# 3_-DAC.net
KiCad netlist of a schematic drawn in Altium Designer
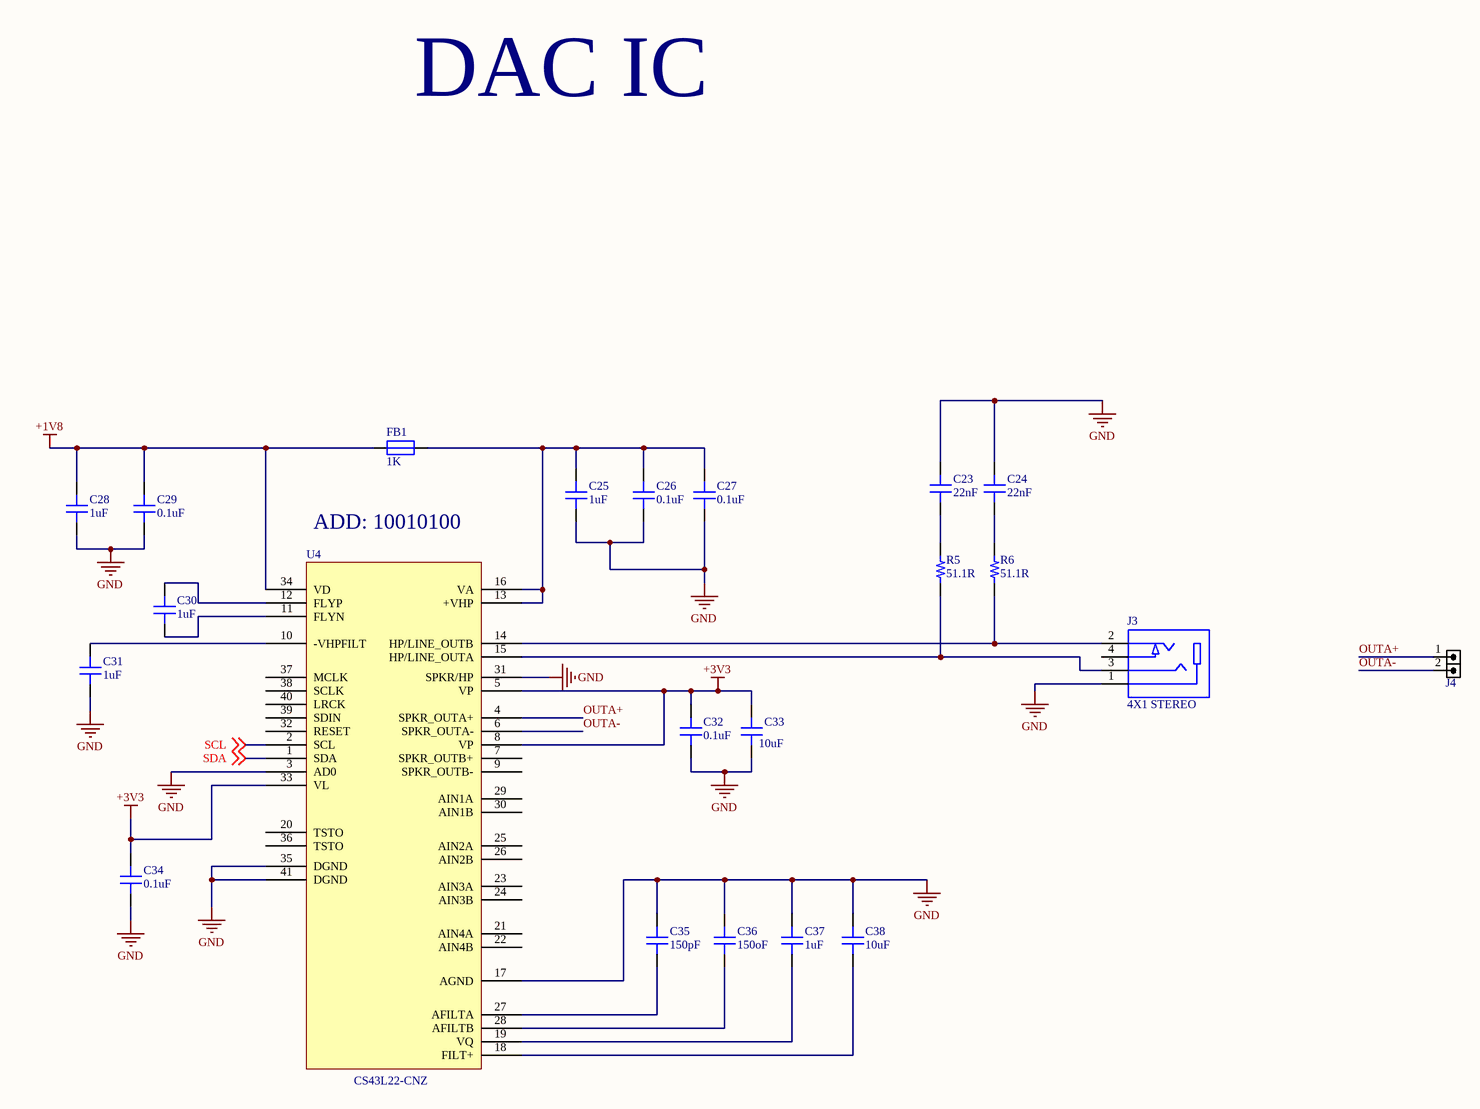
[diagram p0: [3]-DAC.SchDoc]

(export (version "E")
  (design (tool "Eeschema 10.0.6"))
  (components
    (comp (ref "C23")
      (value "22nF")
      (footprint "CAP 0603_1608")
      (description "SMT Capacitor")
      (libsource (lib "Capacitor") (part "Cap 0603"))
    )
    (comp (ref "C24")
      (value "22nF")
      (footprint "CAP 0603_1608")
      (description "SMT Capacitor")
      (libsource (lib "Capacitor") (part "Cap 0603"))
    )
    (comp (ref "C25")
      (value "1uF")
      (footprint "CAP 0603_1608")
      (description "SMT Capacitor")
      (libsource (lib "Capacitor") (part "Cap 0603"))
    )
    (comp (ref "C26")
      (value "0.1uF")
      (footprint "CAP 0603_1608")
      (description "SMT Capacitor")
      (libsource (lib "Capacitor") (part "Cap 0603"))
    )
    (comp (ref "C27")
      (value "0.1uF")
      (footprint "CAP 0603_1608")
      (description "SMT Capacitor")
      (libsource (lib "Capacitor") (part "Cap 0603"))
    )
    (comp (ref "C28")
      (value "1uF")
      (footprint "CAP 0603_1608")
      (description "SMT Capacitor")
      (libsource (lib "Capacitor") (part "Cap 0603"))
    )
    (comp (ref "C29")
      (value "0.1uF")
      (footprint "CAP 0603_1608")
      (description "SMT Capacitor")
      (libsource (lib "Capacitor") (part "Cap 0603"))
    )
    (comp (ref "C30")
      (value "1uF")
      (footprint "CAP 0603_1608")
      (description "SMT Capacitor")
      (libsource (lib "Capacitor") (part "Cap 0603"))
    )
    (comp (ref "C31")
      (value "1uF")
      (footprint "CAP 0603_1608")
      (description "SMT Capacitor")
      (libsource (lib "Capacitor") (part "Cap 0603"))
    )
    (comp (ref "C32")
      (value "0.1uF")
      (footprint "CAP 0603_1608")
      (description "SMT Capacitor")
      (libsource (lib "Capacitor") (part "Cap 0603"))
    )
    (comp (ref "C33")
      (value "10uF")
      (footprint "CAP 0603_1608")
      (description "SMT Capacitor")
      (libsource (lib "Capacitor") (part "Cap 0603"))
    )
    (comp (ref "C34")
      (value "0.1uF")
      (footprint "CAP 0603_1608")
      (description "SMT Capacitor")
      (libsource (lib "Capacitor") (part "Cap 0603"))
    )
    (comp (ref "C35")
      (value "150pF")
      (footprint "CAP 0603_1608")
      (description "SMT Capacitor")
      (libsource (lib "Capacitor") (part "Cap 0603"))
    )
    (comp (ref "C36")
      (value "150oF")
      (footprint "CAP 0603_1608")
      (description "SMT Capacitor")
      (libsource (lib "Capacitor") (part "Cap 0603"))
    )
    (comp (ref "C37")
      (value "1uF")
      (footprint "CAP 0603_1608")
      (description "SMT Capacitor")
      (libsource (lib "Capacitor") (part "Cap 0603"))
    )
    (comp (ref "C38")
      (value "10uF")
      (footprint "CAP 0603_1608")
      (description "SMT Capacitor")
      (libsource (lib "Capacitor") (part "Cap 0603"))
    )
    (comp (ref "FB1")
      (value "1K")
      (footprint "IND_0805")
      (description "1 kOhms @ 100MHz 1 Power Line Ferrite Bead 0805 (2012 Metric) 1.6A")
      (fields
        (field (name "MANUFACTURER") "Laird")
        (field (name "MANUFACTURER PART NUMBER") "BLM21SP102SH1D")
      )
      (libsource (lib "ESTEEMPCBLIB") (part "FB_1K-100MHZ-1.6A-0805"))
    )
    (comp (ref "J3")
      (value "4X1 STEREO")
      (footprint "CON_SJ-2504A-SMT-TR_SMD")
      (fields
        (field (name "MANUFACTURER") "CUI Devices")
        (field (name "MANUFACTURER PART NUMBER") "SJ-2504A-SMT-TR")
      )
      (libsource (lib "ESTEEMPCBLIB") (part "CON-PLG-STEREO_4X1-100-RA-SMD"))
    )
    (comp (ref "J4")
      (value "HDR2")
      (footprint "HDR1SE_M_1X2")
      (description "HEADER, 1mm pitch, test, SMD")
      (libsource (lib "Conn Header") (part "HDRTST_1X2"))
    )
    (comp (ref "R5")
      (value "51.1R")
      (footprint "RES 0603_1608")
      (description "SMT Resistor")
      (libsource (lib "Resistor") (part "Res 0603"))
    )
    (comp (ref "R6")
      (value "51.1R")
      (footprint "RES 0603_1608")
      (description "SMT Resistor")
      (libsource (lib "Resistor") (part "Res 0603"))
    )
    (comp (ref "U4")
      (value "CS43L22-CNZ")
      (footprint "QFN40_19_284_33X9_SMD")
      (description "Audio D/A Converter ICs Low Power Stereo DAC w/ClassD Spkr Driver")
      (fields (field (name "MANUFACTURER") "Cirrus Logic"))
      (libsource (lib "ESTEEMPCBLIB") (part "IC_CS43L22"))
    )
  )
  (nets
    (net (code "1") (name "+1V8") (class "Default")
      (node (ref "C28") (pin "2") (pinfunction "2_2") (pintype "passive"))
      (node (ref "C29") (pin "2") (pinfunction "2_2") (pintype "passive"))
      (node (ref "FB1") (pin "1") (pinfunction "1_1") (pintype "passive"))
      (node (ref "U4") (pin "34") (pinfunction "VD_34") (pintype "passive"))
    )
    (net (code "2") (name "+3V3") (class "Default")
      (node (ref "C32") (pin "2") (pinfunction "2_2") (pintype "passive"))
      (node (ref "C33") (pin "2") (pinfunction "2_2") (pintype "passive"))
      (node (ref "C34") (pin "2") (pinfunction "2_2") (pintype "passive"))
      (node (ref "U4") (pin "33") (pinfunction "VL_33") (pintype "passive"))
      (node (ref "U4") (pin "5") (pinfunction "VP_5") (pintype "passive"))
      (node (ref "U4") (pin "8") (pinfunction "VP_8") (pintype "passive"))
    )
    (net (code "3") (name "/OUTA+") (class "Default")
      (node (ref "J4") (pin "1") (pinfunction "1_1") (pintype "passive"))
      (node (ref "U4") (pin "4") (pinfunction "SPKR_OUTA+_4") (pintype "passive"))
    )
    (net (code "4") (name "/OUTA-") (class "Default")
      (node (ref "J4") (pin "2") (pinfunction "2_2") (pintype "passive"))
      (node (ref "U4") (pin "6") (pinfunction "SPKR_OUTA-_6") (pintype "passive"))
    )
    (net (code "5") (name "GND") (class "Default")
      (node (ref "C23") (pin "2") (pinfunction "2_2") (pintype "passive"))
      (node (ref "C24") (pin "2") (pinfunction "2_2") (pintype "passive"))
      (node (ref "C25") (pin "1") (pinfunction "1_1") (pintype "passive"))
      (node (ref "C26") (pin "1") (pinfunction "1_1") (pintype "passive"))
      (node (ref "C27") (pin "1") (pinfunction "1_1") (pintype "passive"))
      (node (ref "C28") (pin "1") (pinfunction "1_1") (pintype "passive"))
      (node (ref "C29") (pin "1") (pinfunction "1_1") (pintype "passive"))
      (node (ref "C31") (pin "1") (pinfunction "1_1") (pintype "passive"))
      (node (ref "C32") (pin "1") (pinfunction "1_1") (pintype "passive"))
      (node (ref "C33") (pin "1") (pinfunction "1_1") (pintype "passive"))
      (node (ref "C34") (pin "1") (pinfunction "1_1") (pintype "passive"))
      (node (ref "C35") (pin "2") (pinfunction "2_2") (pintype "passive"))
      (node (ref "C36") (pin "2") (pinfunction "2_2") (pintype "passive"))
      (node (ref "C37") (pin "2") (pinfunction "2_2") (pintype "passive"))
      (node (ref "C38") (pin "2") (pinfunction "2_2") (pintype "passive"))
      (node (ref "J3") (pin "1") (pinfunction "1_1") (pintype "passive"))
      (node (ref "U4") (pin "17") (pinfunction "AGND_17") (pintype "passive"))
      (node (ref "U4") (pin "3") (pinfunction "AD0_3") (pintype "passive"))
      (node (ref "U4") (pin "31") (pinfunction "SPKR/HP_31") (pintype "passive"))
      (node (ref "U4") (pin "35") (pinfunction "DGND_35") (pintype "passive"))
      (node (ref "U4") (pin "41") (pinfunction "DGND_41") (pintype "passive"))
    )
    (net (code "6") (name "Net-(C23-Pad1)") (class "Default")
      (node (ref "C23") (pin "1") (pinfunction "1_1") (pintype "passive"))
      (node (ref "R5") (pin "2") (pinfunction "2_2") (pintype "passive"))
    )
    (net (code "7") (name "Net-(C24-Pad1)") (class "Default")
      (node (ref "C24") (pin "1") (pinfunction "1_1") (pintype "passive"))
      (node (ref "R6") (pin "2") (pinfunction "2_2") (pintype "passive"))
    )
    (net (code "8") (name "Net-(U4-+VHP)") (class "Default")
      (node (ref "C25") (pin "2") (pinfunction "2_2") (pintype "passive"))
      (node (ref "C26") (pin "2") (pinfunction "2_2") (pintype "passive"))
      (node (ref "C27") (pin "2") (pinfunction "2_2") (pintype "passive"))
      (node (ref "FB1") (pin "2") (pinfunction "2_2") (pintype "passive"))
      (node (ref "U4") (pin "13") (pinfunction "+VHP_13") (pintype "passive"))
      (node (ref "U4") (pin "16") (pinfunction "VA_16") (pintype "passive"))
    )
    (net (code "9") (name "Net-(U4--VHPFILT)") (class "Default")
      (node (ref "C31") (pin "2") (pinfunction "2_2") (pintype "passive"))
      (node (ref "U4") (pin "10") (pinfunction "-VHPFILT_10") (pintype "passive"))
    )
    (net (code "10") (name "Net-(U4-AFILTA)") (class "Default")
      (node (ref "C35") (pin "1") (pinfunction "1_1") (pintype "passive"))
      (node (ref "U4") (pin "27") (pinfunction "AFILTA_27") (pintype "passive"))
    )
    (net (code "11") (name "Net-(U4-AFILTB)") (class "Default")
      (node (ref "C36") (pin "1") (pinfunction "1_1") (pintype "passive"))
      (node (ref "U4") (pin "28") (pinfunction "AFILTB_28") (pintype "passive"))
    )
    (net (code "12") (name "Net-(U4-FILT+)") (class "Default")
      (node (ref "C38") (pin "1") (pinfunction "1_1") (pintype "passive"))
      (node (ref "U4") (pin "18") (pinfunction "FILT+_18") (pintype "passive"))
    )
    (net (code "13") (name "Net-(U4-FLYN)") (class "Default")
      (node (ref "C30") (pin "2") (pinfunction "2_2") (pintype "passive"))
      (node (ref "U4") (pin "11") (pinfunction "FLYN_11") (pintype "passive"))
    )
    (net (code "14") (name "Net-(U4-FLYP)") (class "Default")
      (node (ref "C30") (pin "1") (pinfunction "1_1") (pintype "passive"))
      (node (ref "U4") (pin "12") (pinfunction "FLYP_12") (pintype "passive"))
    )
    (net (code "15") (name "Net-(U4-HP{slash}LINE_OUTA)") (class "Default")
      (node (ref "J3") (pin "3") (pinfunction "3_3") (pintype "passive"))
      (node (ref "R5") (pin "1") (pinfunction "1_1") (pintype "passive"))
      (node (ref "U4") (pin "15") (pinfunction "HP/LINE_OUTA_15") (pintype "passive"))
    )
    (net (code "16") (name "Net-(U4-HP{slash}LINE_OUTB)") (class "Default")
      (node (ref "J3") (pin "2") (pinfunction "2_2") (pintype "passive"))
      (node (ref "R6") (pin "1") (pinfunction "1_1") (pintype "passive"))
      (node (ref "U4") (pin "14") (pinfunction "HP/LINE_OUTB_14") (pintype "passive"))
    )
    (net (code "17") (name "Net-(U4-VQ)") (class "Default")
      (node (ref "C37") (pin "1") (pinfunction "1_1") (pintype "passive"))
      (node (ref "U4") (pin "19") (pinfunction "VQ_19") (pintype "passive"))
    )
    (net (code "18") (name "SCL") (class "Default")
      (node (ref "U4") (pin "2") (pinfunction "SCL_2") (pintype "passive"))
    )
    (net (code "19") (name "SDA") (class "Default")
      (node (ref "U4") (pin "1") (pinfunction "SDA_1") (pintype "passive"))
    )
    (net (code "20") (name "unconnected-(J3-Pad4)") (class "Default")
      (node (ref "J3") (pin "4") (pinfunction "4_4") (pintype "passive"))
    )
    (net (code "21") (name "unconnected-(U4-AIN1A-Pad29)") (class "Default")
      (node (ref "U4") (pin "29") (pinfunction "AIN1A_29") (pintype "passive"))
    )
    (net (code "22") (name "unconnected-(U4-AIN1B-Pad30)") (class "Default")
      (node (ref "U4") (pin "30") (pinfunction "AIN1B_30") (pintype "passive"))
    )
    (net (code "23") (name "unconnected-(U4-AIN2A-Pad25)") (class "Default")
      (node (ref "U4") (pin "25") (pinfunction "AIN2A_25") (pintype "passive"))
    )
    (net (code "24") (name "unconnected-(U4-AIN2B-Pad26)") (class "Default")
      (node (ref "U4") (pin "26") (pinfunction "AIN2B_26") (pintype "passive"))
    )
    (net (code "25") (name "unconnected-(U4-AIN3A-Pad23)") (class "Default")
      (node (ref "U4") (pin "23") (pinfunction "AIN3A_23") (pintype "passive"))
    )
    (net (code "26") (name "unconnected-(U4-AIN3B-Pad24)") (class "Default")
      (node (ref "U4") (pin "24") (pinfunction "AIN3B_24") (pintype "passive"))
    )
    (net (code "27") (name "unconnected-(U4-AIN4A-Pad21)") (class "Default")
      (node (ref "U4") (pin "21") (pinfunction "AIN4A_21") (pintype "passive"))
    )
    (net (code "28") (name "unconnected-(U4-AIN4B-Pad22)") (class "Default")
      (node (ref "U4") (pin "22") (pinfunction "AIN4B_22") (pintype "passive"))
    )
    (net (code "29") (name "unconnected-(U4-LRCK-Pad40)") (class "Default")
      (node (ref "U4") (pin "40") (pinfunction "LRCK_40") (pintype "passive"))
    )
    (net (code "30") (name "unconnected-(U4-MCLK-Pad37)") (class "Default")
      (node (ref "U4") (pin "37") (pinfunction "MCLK_37") (pintype "passive"))
    )
    (net (code "31") (name "unconnected-(U4-RESET-Pad32)") (class "Default")
      (node (ref "U4") (pin "32") (pinfunction "RESET_32") (pintype "passive"))
    )
    (net (code "32") (name "unconnected-(U4-SCLK-Pad38)") (class "Default")
      (node (ref "U4") (pin "38") (pinfunction "SCLK_38") (pintype "passive"))
    )
    (net (code "33") (name "unconnected-(U4-SDIN-Pad39)") (class "Default")
      (node (ref "U4") (pin "39") (pinfunction "SDIN_39") (pintype "passive"))
    )
    (net (code "34") (name "unconnected-(U4-SPKR_OUTB+-Pad7)") (class "Default")
      (node (ref "U4") (pin "7") (pinfunction "SPKR_OUTB+_7") (pintype "passive"))
    )
    (net (code "35") (name "unconnected-(U4-SPKR_OUTB--Pad9)") (class "Default")
      (node (ref "U4") (pin "9") (pinfunction "SPKR_OUTB-_9") (pintype "passive"))
    )
    (net (code "36") (name "unconnected-(U4-TSTO-Pad20)") (class "Default")
      (node (ref "U4") (pin "20") (pinfunction "TSTO_20") (pintype "passive"))
    )
    (net (code "37") (name "unconnected-(U4-TSTO-Pad36)") (class "Default")
      (node (ref "U4") (pin "36") (pinfunction "TSTO_36") (pintype "passive"))
    )
  )
)
